# main.net
KiCad netlist of a schematic drawn in Altium Designer
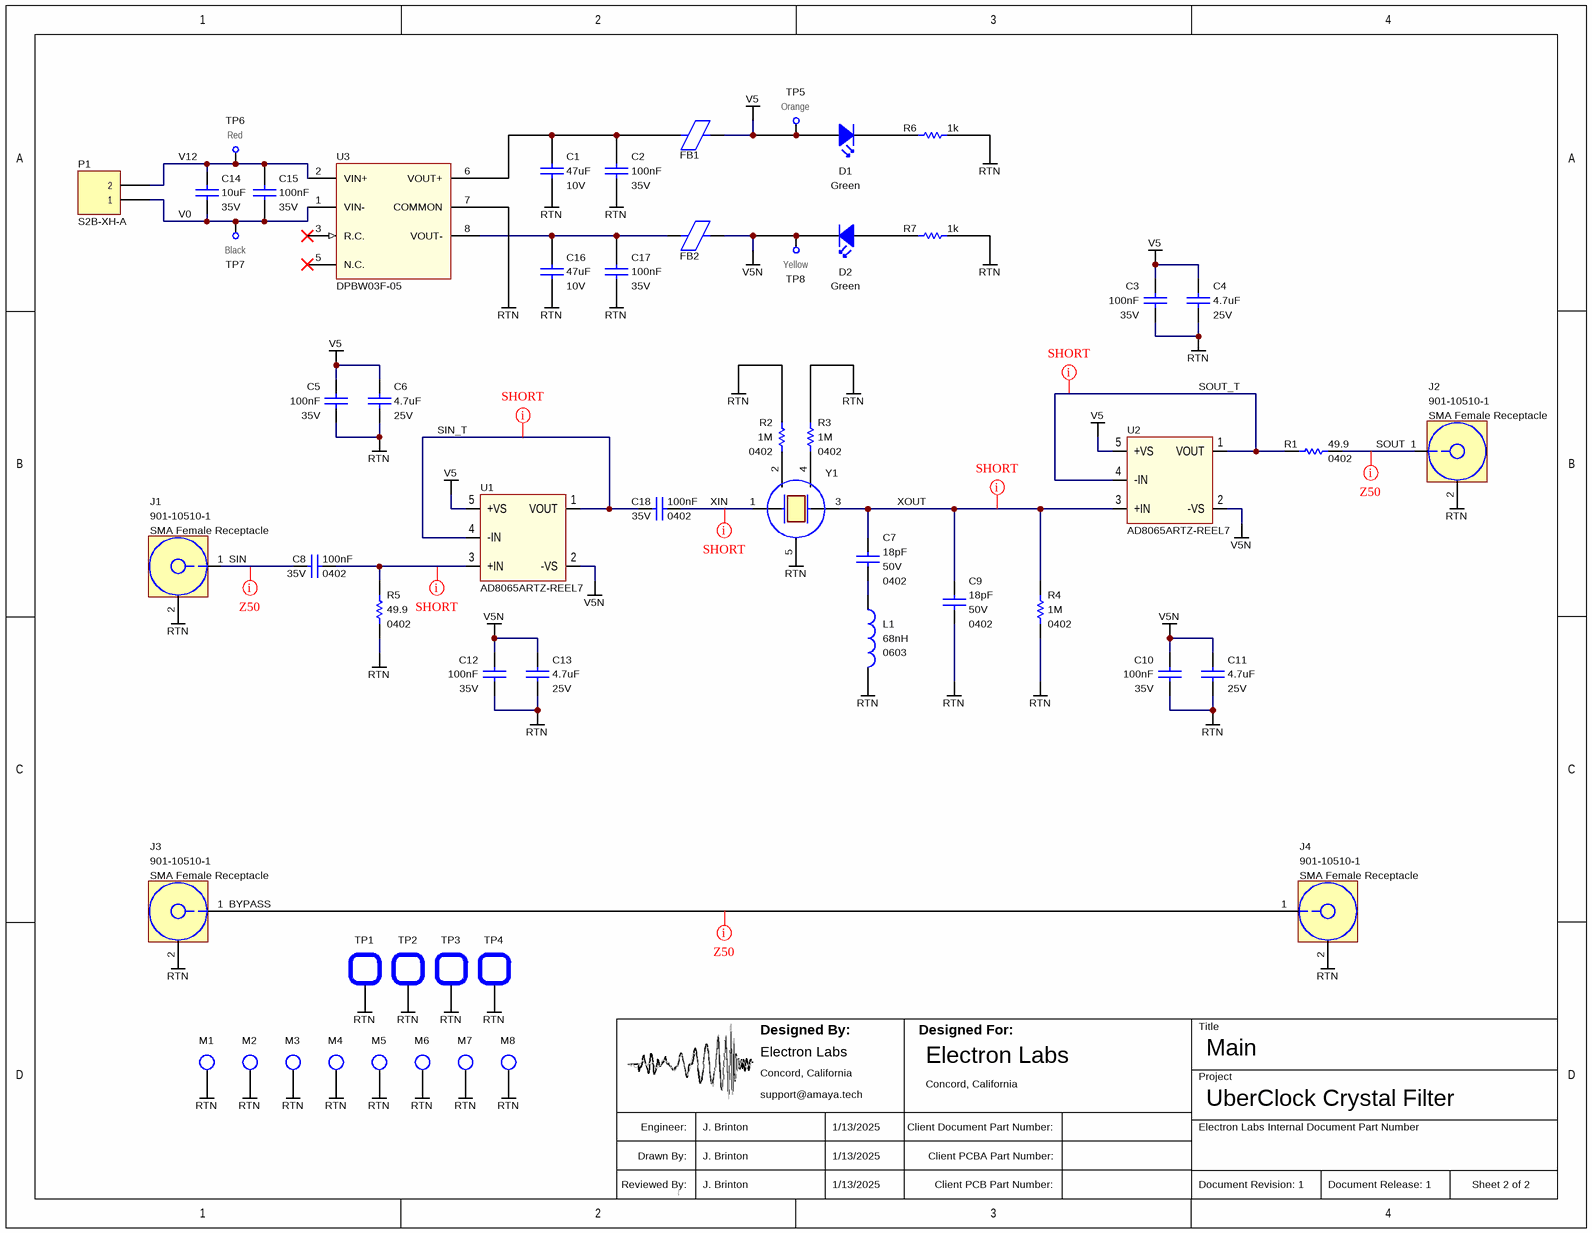
[diagram p0: main.SchDoc]

(export (version "E")
  (design (tool "Eeschema 10.0.6"))
  (components
    (comp (ref "C1")
      (value "47uF")
      (footprint "CAPC3225X25N")
      (description "CAPACITOR CERAMIC 47UF 20% 10V X7S 1210")
      (fields (field (name "TOLERANCE") "20%") (field (name "MFG") "TDK") (field (name "VOLTAGE") "10V"))
      (libsource (lib "tdk") (part "CAP"))
    )
    (comp (ref "C2")
      (value "100nF")
      (footprint "CAPC1005X05N")
      (description "CAPACITOR CERAMIC 100NF 10% 35V X7R 0402")
      (fields (field (name "TOLERANCE") "10%") (field (name "MFG") "TDK") (field (name "VOLTAGE") "35V"))
      (libsource (lib "tdk") (part "CAP"))
    )
    (comp (ref "C3")
      (value "100nF")
      (footprint "CAPC1005X05N")
      (description "CAPACITOR CERAMIC 100NF 10% 35V X7R 0402")
      (fields (field (name "TOLERANCE") "10%") (field (name "MFG") "TDK") (field (name "VOLTAGE") "35V"))
      (libsource (lib "tdk") (part "CAP"))
    )
    (comp (ref "C4")
      (value "4.7uF")
      (footprint "CAPC2012X125N")
      (description "CAPACITOR CERAMIC 4.7UF 10% 25V X5R 0805")
      (fields (field (name "TOLERANCE") "10%") (field (name "MFG") "TDK") (field (name "VOLTAGE") "25V"))
      (libsource (lib "tdk") (part "CAP"))
    )
    (comp (ref "C5")
      (value "100nF")
      (footprint "CAPC1005X05N")
      (description "CAPACITOR CERAMIC 100NF 10% 35V X7R 0402")
      (fields (field (name "TOLERANCE") "10%") (field (name "MFG") "TDK") (field (name "VOLTAGE") "35V"))
      (libsource (lib "tdk") (part "CAP"))
    )
    (comp (ref "C6")
      (value "4.7uF")
      (footprint "CAPC2012X125N")
      (description "CAPACITOR CERAMIC 4.7UF 10% 25V X5R 0805")
      (fields (field (name "TOLERANCE") "10%") (field (name "MFG") "TDK") (field (name "VOLTAGE") "25V"))
      (libsource (lib "tdk") (part "CAP"))
    )
    (comp (ref "C7")
      (value "18pF")
      (footprint "CAPC1005X05N")
      (description "CAPACITOR CERAMIC 18PF 5% 50V C0G 0402")
      (fields
        (field (name "TOLERANCE") "5%")
        (field (name "MFG") "TDK")
        (field (name "VOLTAGE") "50V")
        (field (name "PACKAGE") "0402")
      )
      (libsource (lib "tdk") (part "CAP"))
    )
    (comp (ref "C8")
      (value "100nF")
      (footprint "CAPC1005X05N")
      (description "CAPACITOR CERAMIC 100NF 10% 35V X7R 0402")
      (fields
        (field (name "TOLERANCE") "10%")
        (field (name "MFG") "TDK")
        (field (name "VOLTAGE") "35V")
        (field (name "PACKAGE") "0402")
      )
      (libsource (lib "tdk") (part "CAP"))
    )
    (comp (ref "C9")
      (value "18pF")
      (footprint "CAPC1005X05N")
      (description "CAPACITOR CERAMIC 18PF 5% 50V C0G 0402")
      (fields
        (field (name "TOLERANCE") "5%")
        (field (name "MFG") "TDK")
        (field (name "VOLTAGE") "50V")
        (field (name "PACKAGE") "0402")
      )
      (libsource (lib "tdk") (part "CAP"))
    )
    (comp (ref "C10")
      (value "100nF")
      (footprint "CAPC1005X05N")
      (description "CAPACITOR CERAMIC 100NF 10% 35V X7R 0402")
      (fields (field (name "TOLERANCE") "10%") (field (name "MFG") "TDK") (field (name "VOLTAGE") "35V"))
      (libsource (lib "tdk") (part "CAP"))
    )
    (comp (ref "C11")
      (value "4.7uF")
      (footprint "CAPC2012X125N")
      (description "CAPACITOR CERAMIC 4.7UF 10% 25V X5R 0805")
      (fields (field (name "TOLERANCE") "10%") (field (name "MFG") "TDK") (field (name "VOLTAGE") "25V"))
      (libsource (lib "tdk") (part "CAP"))
    )
    (comp (ref "C12")
      (value "100nF")
      (footprint "CAPC1005X05N")
      (description "CAPACITOR CERAMIC 100NF 10% 35V X7R 0402")
      (fields (field (name "TOLERANCE") "10%") (field (name "MFG") "TDK") (field (name "VOLTAGE") "35V"))
      (libsource (lib "tdk") (part "CAP"))
    )
    (comp (ref "C13")
      (value "4.7uF")
      (footprint "CAPC2012X125N")
      (description "CAPACITOR CERAMIC 4.7UF 10% 25V X5R 0805")
      (fields (field (name "TOLERANCE") "10%") (field (name "MFG") "TDK") (field (name "VOLTAGE") "25V"))
      (libsource (lib "tdk") (part "CAP"))
    )
    (comp (ref "C14")
      (value "10uF")
      (footprint "CAPC3216X16N")
      (description "CAPACITOR CERAMIC 10UF 20% 35V X5R 1206")
      (fields (field (name "TOLERANCE") "20%") (field (name "MFG") "TDK") (field (name "VOLTAGE") "35V"))
      (libsource (lib "tdk") (part "CAP"))
    )
    (comp (ref "C15")
      (value "100nF")
      (footprint "CAPC1005X05N")
      (description "CAPACITOR CERAMIC 100NF 10% 35V X7R 0402")
      (fields (field (name "TOLERANCE") "10%") (field (name "MFG") "TDK") (field (name "VOLTAGE") "35V"))
      (libsource (lib "tdk") (part "CAP"))
    )
    (comp (ref "C16")
      (value "47uF")
      (footprint "CAPC3225X25N")
      (description "CAPACITOR CERAMIC 47UF 20% 10V X7S 1210")
      (fields (field (name "TOLERANCE") "20%") (field (name "MFG") "TDK") (field (name "VOLTAGE") "10V"))
      (libsource (lib "tdk") (part "CAP"))
    )
    (comp (ref "C17")
      (value "100nF")
      (footprint "CAPC1005X05N")
      (description "CAPACITOR CERAMIC 100NF 10% 35V X7R 0402")
      (fields (field (name "TOLERANCE") "10%") (field (name "MFG") "TDK") (field (name "VOLTAGE") "35V"))
      (libsource (lib "tdk") (part "CAP"))
    )
    (comp (ref "C18")
      (value "100nF")
      (footprint "CAPC1005X05N")
      (description "CAPACITOR CERAMIC 100NF 10% 35V X7R 0402")
      (fields
        (field (name "TOLERANCE") "10%")
        (field (name "MFG") "TDK")
        (field (name "VOLTAGE") "35V")
        (field (name "PACKAGE") "0402")
      )
      (libsource (lib "tdk") (part "CAP"))
    )
    (comp (ref "D1")
      (value "LTST-C191KGKT")
      (footprint "0603_LED")
      (description "LED GREEN CLEAR SMD")
      (fields (field (name "MFG") "LITE-ON INC") (field (name "COLOR") "Green"))
      (libsource (lib "101-0000212_UBERCLOCK_CRYSTAL_FILTER") (part "LTST-C191KGKT"))
    )
    (comp (ref "D2")
      (value "LTST-C191KGKT")
      (footprint "0603_LED")
      (description "LED GREEN CLEAR SMD")
      (fields (field (name "MFG") "LITE-ON INC") (field (name "COLOR") "Green"))
      (libsource (lib "101-0000212_UBERCLOCK_CRYSTAL_FILTER") (part "LTST-C191KGKT"))
    )
    (comp (ref "FB1")
      (value "BLM18AG102SN1")
      (footprint "INDC1608X08N")
      (description "FERRITE BEAD 1000-OHM 450MA 0603")
      (fields (field (name "MFG") "MURATA"))
      (libsource (lib "murata") (part "FERRITE"))
    )
    (comp (ref "FB2")
      (value "BLM18AG102SN1")
      (footprint "INDC1608X08N")
      (description "FERRITE BEAD 1000-OHM 450MA 0603")
      (fields (field (name "MFG") "MURATA"))
      (libsource (lib "murata") (part "FERRITE"))
    )
    (comp (ref "J1")
      (value "~")
      (footprint "901-10510-1")
      (description "SMA BOARD EDGE CONNECTOR FEMALE")
      (fields
        (field (name "MFG") "AMPHENOL")
        (field (name "NOTES") "SMA Female Receptacle")
        (field (name "MPN") "901-10510-1")
      )
      (libsource (lib "") (part "901-10510-1_1"))
    )
    (comp (ref "J2")
      (value "~")
      (footprint "901-10510-1")
      (description "SMA BOARD EDGE CONNECTOR FEMALE")
      (fields
        (field (name "MFG") "AMPHENOL")
        (field (name "NOTES") "SMA Female Receptacle")
        (field (name "MPN") "901-10510-1")
      )
      (libsource (lib "amphenol") (part "901-10510-1"))
    )
    (comp (ref "J3")
      (value "~")
      (footprint "901-10510-1")
      (description "SMA BOARD EDGE CONNECTOR FEMALE")
      (fields
        (field (name "MFG") "AMPHENOL")
        (field (name "NOTES") "SMA Female Receptacle")
        (field (name "MPN") "901-10510-1")
      )
      (libsource (lib "") (part "901-10510-1_1"))
    )
    (comp (ref "J4")
      (value "~")
      (footprint "901-10510-1")
      (description "SMA BOARD EDGE CONNECTOR FEMALE")
      (fields
        (field (name "MFG") "AMPHENOL")
        (field (name "NOTES") "SMA Female Receptacle")
        (field (name "MPN") "901-10510-1")
      )
      (libsource (lib "amphenol") (part "901-10510-1"))
    )
    (comp (ref "L1")
      (value "68nH")
      (footprint "INDC1608X08N")
      (description "FIXED IND 68NH 340MA 0.38OHM SMD")
      (fields
        (field (name "MPN") "LQW18AN68NJ00D")
        (field (name "MFG") "MURATA")
        (field (name "PACKAGE") "0603")
      )
      (libsource (lib "101-0000212_UBERCLOCK_CRYSTAL_FILTER") (part "LQW18AN68NJ00D"))
    )
    (comp (ref "M1")
      (value "MOUNTM3")
      (footprint "MOUNTM3")
      (description "M3 MOUNTING HOLE")
      (libsource (lib "101-0000212_UBERCLOCK_CRYSTAL_FILTER") (part "MOUNTM3"))
    )
    (comp (ref "M2")
      (value "MOUNTM3")
      (footprint "MOUNTM3")
      (description "M3 MOUNTING HOLE")
      (libsource (lib "101-0000212_UBERCLOCK_CRYSTAL_FILTER") (part "MOUNTM3"))
    )
    (comp (ref "M3")
      (value "MOUNTM3")
      (footprint "MOUNTM3")
      (description "M3 MOUNTING HOLE")
      (libsource (lib "101-0000212_UBERCLOCK_CRYSTAL_FILTER") (part "MOUNTM3"))
    )
    (comp (ref "M4")
      (value "MOUNTM3")
      (footprint "MOUNTM3")
      (description "M3 MOUNTING HOLE")
      (libsource (lib "101-0000212_UBERCLOCK_CRYSTAL_FILTER") (part "MOUNTM3"))
    )
    (comp (ref "M5")
      (value "MOUNTM3")
      (footprint "MOUNTM3")
      (description "M3 MOUNTING HOLE")
      (libsource (lib "101-0000212_UBERCLOCK_CRYSTAL_FILTER") (part "MOUNTM3"))
    )
    (comp (ref "M6")
      (value "MOUNTM3")
      (footprint "MOUNTM3")
      (description "M3 MOUNTING HOLE")
      (libsource (lib "101-0000212_UBERCLOCK_CRYSTAL_FILTER") (part "MOUNTM3"))
    )
    (comp (ref "M7")
      (value "MOUNTM3")
      (footprint "MOUNTM3")
      (description "M3 MOUNTING HOLE")
      (libsource (lib "101-0000212_UBERCLOCK_CRYSTAL_FILTER") (part "MOUNTM3"))
    )
    (comp (ref "M8")
      (value "MOUNTM3")
      (footprint "MOUNTM3")
      (description "M3 MOUNTING HOLE")
      (libsource (lib "101-0000212_UBERCLOCK_CRYSTAL_FILTER") (part "MOUNTM3"))
    )
    (comp (ref "P1")
      (value "S2B-XH-A")
      (footprint "jst:S2B-XH-A")
      (description "CONN HEADER R/A 2POS 2.5MM")
      (fields (field (name "MPN") "S2B-XH-A") (field (name "MFG") "JST"))
      (libsource (lib "jst") (part "S2B-XH-A"))
    )
    (comp (ref "R1")
      (value "49.9")
      (footprint "RESC1005X035N")
      (description "RESISTOR THICK FILM 49.9 OHM 1% 0402")
      (fields
        (field (name "TOLERANCE") "1%")
        (field (name "MFG") "PANASONIC")
        (field (name "PACKAGE") "0402")
      )
      (libsource (lib "panasonic") (part "RES"))
    )
    (comp (ref "R2")
      (value "1M")
      (footprint "RESC1005X035N")
      (description "RESISTOR THICK FILM 1M OHM 1% 0402")
      (fields
        (field (name "TOLERANCE") "1%")
        (field (name "MFG") "PANASONIC")
        (field (name "PACKAGE") "0402")
      )
      (libsource (lib "panasonic") (part "RES"))
    )
    (comp (ref "R3")
      (value "1M")
      (footprint "RESC1005X035N")
      (description "RESISTOR THICK FILM 1M OHM 1% 0402")
      (fields
        (field (name "TOLERANCE") "1%")
        (field (name "MFG") "PANASONIC")
        (field (name "PACKAGE") "0402")
      )
      (libsource (lib "panasonic") (part "RES"))
    )
    (comp (ref "R4")
      (value "1M")
      (footprint "RESC1005X035N")
      (description "RESISTOR THICK FILM 1M OHM 1% 0402")
      (fields
        (field (name "TOLERANCE") "1%")
        (field (name "MFG") "PANASONIC")
        (field (name "PACKAGE") "0402")
      )
      (libsource (lib "panasonic") (part "RES"))
    )
    (comp (ref "R5")
      (value "49.9")
      (footprint "RESC1005X035N")
      (description "RESISTOR THICK FILM 49.9 OHM 1% 0402")
      (fields
        (field (name "TOLERANCE") "1%")
        (field (name "MFG") "PANASONIC")
        (field (name "PACKAGE") "0402")
      )
      (libsource (lib "panasonic") (part "RES"))
    )
    (comp (ref "R6")
      (value "1k")
      (footprint "RESC1005X035N")
      (description "RESISTOR THICK FILM 1k OHM 1% 0402")
      (fields (field (name "TOLERANCE") "1%") (field (name "MFG") "PANASONIC"))
      (libsource (lib "panasonic") (part "RES"))
    )
    (comp (ref "R7")
      (value "1k")
      (footprint "RESC1005X035N")
      (description "RESISTOR THICK FILM 1k OHM 1% 0402")
      (fields (field (name "TOLERANCE") "1%") (field (name "MFG") "PANASONIC"))
      (libsource (lib "panasonic") (part "RES"))
    )
    (comp (ref "TP1")
      (value "5015")
      (footprint "5015")
      (description "TEST POINT SMD")
      (fields (field (name "MFG") "KEYSTONE"))
      (libsource (lib "keystone") (part "5015"))
    )
    (comp (ref "TP2")
      (value "5015")
      (footprint "5015")
      (description "TEST POINT SMD")
      (fields (field (name "MFG") "KEYSTONE"))
      (libsource (lib "keystone") (part "5015"))
    )
    (comp (ref "TP3")
      (value "5015")
      (footprint "5015")
      (description "TEST POINT SMD")
      (fields (field (name "MFG") "KEYSTONE"))
      (libsource (lib "keystone") (part "5015"))
    )
    (comp (ref "TP4")
      (value "5015")
      (footprint "5015")
      (description "TEST POINT SMD")
      (fields (field (name "MFG") "KEYSTONE"))
      (libsource (lib "keystone") (part "5015"))
    )
    (comp (ref "TP5")
      (value "~")
      (footprint "keystone:5003")
      (description "THRUHOLE MOUNT TEST POINT, 4.6MM TALL, ORANGE")
      (fields (field (name "MPN") "5003") (field (name "MFG") "KEYSTONE") (field (name "NOTES") "Orange"))
      (libsource (lib "keystone") (part "5003"))
    )
    (comp (ref "TP6")
      (value "~")
      (footprint "keystone:5000")
      (description "THRUHOLE MOUNT TEST POINT, 4.6MM TALL, RED")
      (fields (field (name "MPN") "5000") (field (name "MFG") "KEYSTONE") (field (name "NOTES") "Red"))
      (libsource (lib "keystone") (part "5000"))
    )
    (comp (ref "TP7")
      (value "~")
      (footprint "keystone:5001")
      (description "THRUHOLE MOUNT TEST POINT, 4.6MM TALL, BLACK")
      (fields (field (name "MPN") "5001") (field (name "MFG") "KEYSTONE") (field (name "NOTES") "Black"))
      (libsource (lib "keystone") (part "5001"))
    )
    (comp (ref "TP8")
      (value "~")
      (footprint "keystone:5004")
      (description "THRUHOLE MOUNT TEST POINT, 4.6MM TALL, YELLOW")
      (fields (field (name "MPN") "5004") (field (name "MFG") "KEYSTONE") (field (name "NOTES") "Yellow"))
      (libsource (lib "keystone") (part "5004"))
    )
    (comp (ref "U1")
      (value "AD8065ARTZ-REEL7")
      (footprint "SOT23-5")
      (description "IC OPAMP VFB 1 CIRCUIT SOT23-5")
      (fields (field (name "MFG") "ANALOG DEVICES"))
      (libsource (lib "ALT_NA_LIB") (part "AD8065ARTZ-REEL7"))
    )
    (comp (ref "U2")
      (value "AD8065ARTZ-REEL7")
      (footprint "SOT23-5")
      (description "IC OPAMP VFB 1 CIRCUIT SOT23-5")
      (fields (field (name "MFG") "ANALOG DEVICES"))
      (libsource (lib "ALT_NA_LIB") (part "AD8065ARTZ-REEL7"))
    )
    (comp (ref "U3")
      (value "DPBW03F-05")
      (footprint "SPBW03F-05_MWU")
      (description "DC DC CONVERTER +/-5V 3W")
      (fields (field (name "MFG") "MEAN WELL") (field (name "MPN") "DPBW03F-05"))
      (libsource (lib "101-0000212_UBERCLOCK_CRYSTAL_FILTER") (part "SPBW03F-05"))
    )
    (comp (ref "Y1")
      (value "311205346")
      (footprint "311205346")
      (description "CUSTOM CRYSTAL RESONATOR")
      (fields (field (name "MFG") "VECTRON"))
      (libsource (lib "101-0000212_UBERCLOCK_CRYSTAL_FILTER") (part "311205346"))
    )
  )
  (nets
    (net (code "1") (name "/BYPASS") (class "Default")
      (node (ref "J3") (pin "1") (pinfunction "CENTER_1") (pintype "passive"))
      (node (ref "J4") (pin "1") (pinfunction "CENTER_1") (pintype "passive"))
    )
    (net (code "2") (name "/SIN") (class "Default")
      (node (ref "C8") (pin "2") (pinfunction "2_2") (pintype "passive"))
      (node (ref "J1") (pin "1") (pinfunction "CENTER_1") (pintype "passive"))
    )
    (net (code "3") (name "/SIN_T") (class "Default")
      (node (ref "C18") (pin "2") (pinfunction "2_2") (pintype "passive"))
      (node (ref "U1") (pin "1") (pinfunction "VOUT_1") (pintype "passive"))
      (node (ref "U1") (pin "4") (pinfunction "-IN_4") (pintype "passive"))
    )
    (net (code "4") (name "/SOUT") (class "Default")
      (node (ref "J2") (pin "1") (pinfunction "CENTER_1") (pintype "passive"))
      (node (ref "R1") (pin "1") (pinfunction "1_1") (pintype "passive"))
    )
    (net (code "5") (name "/SOUT_T") (class "Default")
      (node (ref "R1") (pin "2") (pinfunction "2_2") (pintype "passive"))
      (node (ref "U2") (pin "1") (pinfunction "VOUT_1") (pintype "passive"))
      (node (ref "U2") (pin "4") (pinfunction "-IN_4") (pintype "passive"))
    )
    (net (code "6") (name "/V0") (class "Default")
      (node (ref "C14") (pin "1") (pinfunction "1_1") (pintype "passive"))
      (node (ref "C15") (pin "2") (pinfunction "2_2") (pintype "passive"))
      (node (ref "P1") (pin "1") (pinfunction "1_1") (pintype "passive"))
      (node (ref "TP7") (pin "1") (pinfunction "1_1") (pintype "passive"))
      (node (ref "U3") (pin "1") (pinfunction "VIN-_1") (pintype "power_in"))
    )
    (net (code "7") (name "/V12") (class "Default")
      (node (ref "C14") (pin "2") (pinfunction "2_2") (pintype "passive"))
      (node (ref "C15") (pin "1") (pinfunction "1_1") (pintype "passive"))
      (node (ref "P1") (pin "2") (pinfunction "2_2") (pintype "passive"))
      (node (ref "TP6") (pin "1") (pinfunction "1_1") (pintype "passive"))
      (node (ref "U3") (pin "2") (pinfunction "VIN+_2") (pintype "power_in"))
    )
    (net (code "8") (name "/XIN") (class "Default")
      (node (ref "C18") (pin "1") (pinfunction "1_1") (pintype "passive"))
      (node (ref "Y1") (pin "1") (pinfunction "1_1") (pintype "passive"))
    )
    (net (code "9") (name "/XOUT") (class "Default")
      (node (ref "C7") (pin "2") (pinfunction "2_2") (pintype "passive"))
      (node (ref "C9") (pin "2") (pinfunction "2_2") (pintype "passive"))
      (node (ref "R4") (pin "2") (pinfunction "2_2") (pintype "passive"))
      (node (ref "U2") (pin "3") (pinfunction "+IN_3") (pintype "passive"))
      (node (ref "Y1") (pin "3") (pinfunction "3_3") (pintype "passive"))
    )
    (net (code "10") (name "Net-(C7-Pad1)") (class "Default")
      (node (ref "C7") (pin "1") (pinfunction "1_1") (pintype "passive"))
      (node (ref "L1") (pin "1") (pinfunction "1_1") (pintype "passive"))
    )
    (net (code "11") (name "Net-(D1-K)") (class "Default")
      (node (ref "D1") (pin "2") (pinfunction "K_2") (pintype "passive"))
      (node (ref "R6") (pin "1") (pinfunction "1_1") (pintype "passive"))
    )
    (net (code "12") (name "Net-(D2-A)") (class "Default")
      (node (ref "D2") (pin "1") (pinfunction "A_1") (pintype "passive"))
      (node (ref "R7") (pin "1") (pinfunction "1_1") (pintype "passive"))
    )
    (net (code "13") (name "Net-(R2-Pad1)") (class "Default")
      (node (ref "R2") (pin "1") (pinfunction "1_1") (pintype "passive"))
      (node (ref "Y1") (pin "2") (pinfunction "2_2") (pintype "passive"))
    )
    (net (code "14") (name "Net-(R3-Pad1)") (class "Default")
      (node (ref "R3") (pin "1") (pinfunction "1_1") (pintype "passive"))
      (node (ref "Y1") (pin "4") (pinfunction "4_4") (pintype "passive"))
    )
    (net (code "15") (name "Net-(U1-+IN)") (class "Default")
      (node (ref "C8") (pin "1") (pinfunction "1_1") (pintype "passive"))
      (node (ref "R5") (pin "2") (pinfunction "2_2") (pintype "passive"))
      (node (ref "U1") (pin "3") (pinfunction "+IN_3") (pintype "passive"))
    )
    (net (code "16") (name "Net-(U3-VOUT+)") (class "Default")
      (node (ref "C1") (pin "2") (pinfunction "2_2") (pintype "passive"))
      (node (ref "C2") (pin "1") (pinfunction "1_1") (pintype "passive"))
      (node (ref "FB1") (pin "1") (pinfunction "1_1") (pintype "passive"))
      (node (ref "U3") (pin "6") (pinfunction "VOUT+_6") (pintype "power_in"))
    )
    (net (code "17") (name "Net-(U3-VOUT-)") (class "Default")
      (node (ref "C16") (pin "2") (pinfunction "2_2") (pintype "passive"))
      (node (ref "C17") (pin "1") (pinfunction "1_1") (pintype "passive"))
      (node (ref "FB2") (pin "1") (pinfunction "1_1") (pintype "passive"))
      (node (ref "U3") (pin "8") (pinfunction "VOUT-_8") (pintype "power_in"))
    )
    (net (code "18") (name "RTN") (class "Default")
      (node (ref "C1") (pin "1") (pinfunction "1_1") (pintype "passive"))
      (node (ref "C10") (pin "2") (pinfunction "2_2") (pintype "passive"))
      (node (ref "C11") (pin "1") (pinfunction "1_1") (pintype "passive"))
      (node (ref "C12") (pin "2") (pinfunction "2_2") (pintype "passive"))
      (node (ref "C13") (pin "1") (pinfunction "1_1") (pintype "passive"))
      (node (ref "C16") (pin "1") (pinfunction "1_1") (pintype "passive"))
      (node (ref "C17") (pin "2") (pinfunction "2_2") (pintype "passive"))
      (node (ref "C2") (pin "2") (pinfunction "2_2") (pintype "passive"))
      (node (ref "C3") (pin "2") (pinfunction "2_2") (pintype "passive"))
      (node (ref "C4") (pin "1") (pinfunction "1_1") (pintype "passive"))
      (node (ref "C5") (pin "2") (pinfunction "2_2") (pintype "passive"))
      (node (ref "C6") (pin "1") (pinfunction "1_1") (pintype "passive"))
      (node (ref "C9") (pin "1") (pinfunction "1_1") (pintype "passive"))
      (node (ref "J1") (pin "2") (pinfunction "GND_2") (pintype "passive"))
      (node (ref "J2") (pin "2") (pinfunction "GND_2") (pintype "passive"))
      (node (ref "J3") (pin "2") (pinfunction "GND_2") (pintype "passive"))
      (node (ref "J4") (pin "2") (pinfunction "GND_2") (pintype "passive"))
      (node (ref "L1") (pin "2") (pinfunction "2_2") (pintype "passive"))
      (node (ref "M1") (pin "1") (pinfunction "1_1") (pintype "passive"))
      (node (ref "M2") (pin "1") (pinfunction "1_1") (pintype "passive"))
      (node (ref "M3") (pin "1") (pinfunction "1_1") (pintype "passive"))
      (node (ref "M4") (pin "1") (pinfunction "1_1") (pintype "passive"))
      (node (ref "M5") (pin "1") (pinfunction "1_1") (pintype "passive"))
      (node (ref "M6") (pin "1") (pinfunction "1_1") (pintype "passive"))
      (node (ref "M7") (pin "1") (pinfunction "1_1") (pintype "passive"))
      (node (ref "M8") (pin "1") (pinfunction "1_1") (pintype "passive"))
      (node (ref "R2") (pin "2") (pinfunction "2_2") (pintype "passive"))
      (node (ref "R3") (pin "2") (pinfunction "2_2") (pintype "passive"))
      (node (ref "R4") (pin "1") (pinfunction "1_1") (pintype "passive"))
      (node (ref "R5") (pin "1") (pinfunction "1_1") (pintype "passive"))
      (node (ref "R6") (pin "2") (pinfunction "2_2") (pintype "passive"))
      (node (ref "R7") (pin "2") (pinfunction "2_2") (pintype "passive"))
      (node (ref "TP1") (pin "1") (pinfunction "1_1") (pintype "passive"))
      (node (ref "TP2") (pin "1") (pinfunction "1_1") (pintype "passive"))
      (node (ref "TP3") (pin "1") (pinfunction "1_1") (pintype "passive"))
      (node (ref "TP4") (pin "1") (pinfunction "1_1") (pintype "passive"))
      (node (ref "U3") (pin "7") (pinfunction "COMMON_7") (pintype "power_in"))
      (node (ref "Y1") (pin "5") (pinfunction "5_5") (pintype "passive"))
    )
    (net (code "19") (name "V5") (class "Default")
      (node (ref "C3") (pin "1") (pinfunction "1_1") (pintype "passive"))
      (node (ref "C4") (pin "2") (pinfunction "2_2") (pintype "passive"))
      (node (ref "C5") (pin "1") (pinfunction "1_1") (pintype "passive"))
      (node (ref "C6") (pin "2") (pinfunction "2_2") (pintype "passive"))
      (node (ref "D1") (pin "1") (pinfunction "A_1") (pintype "passive"))
      (node (ref "FB1") (pin "2") (pinfunction "2_2") (pintype "passive"))
      (node (ref "TP5") (pin "1") (pinfunction "1_1") (pintype "passive"))
      (node (ref "U1") (pin "5") (pinfunction "+VS_5") (pintype "power_in"))
      (node (ref "U2") (pin "5") (pinfunction "+VS_5") (pintype "power_in"))
    )
    (net (code "20") (name "V5N") (class "Default")
      (node (ref "C10") (pin "1") (pinfunction "1_1") (pintype "passive"))
      (node (ref "C11") (pin "2") (pinfunction "2_2") (pintype "passive"))
      (node (ref "C12") (pin "1") (pinfunction "1_1") (pintype "passive"))
      (node (ref "C13") (pin "2") (pinfunction "2_2") (pintype "passive"))
      (node (ref "D2") (pin "2") (pinfunction "K_2") (pintype "passive"))
      (node (ref "FB2") (pin "2") (pinfunction "2_2") (pintype "passive"))
      (node (ref "TP8") (pin "1") (pinfunction "1_1") (pintype "passive"))
      (node (ref "U1") (pin "2") (pinfunction "-VS_2") (pintype "power_in"))
      (node (ref "U2") (pin "2") (pinfunction "-VS_2") (pintype "power_in"))
    )
    (net (code "21") (name "unconnected-(U3-N.C.-Pad5)") (class "Default")
      (node (ref "U3") (pin "5") (pinfunction "N.C._5") (pintype "passive+no_connect"))
    )
    (net (code "22") (name "unconnected-(U3-R.C.-Pad3)") (class "Default")
      (node (ref "U3") (pin "3") (pinfunction "R.C._3") (pintype "input+no_connect"))
    )
  )
)
